# Uni-2_31.net
KiCad netlist of a schematic drawn in EAGLE
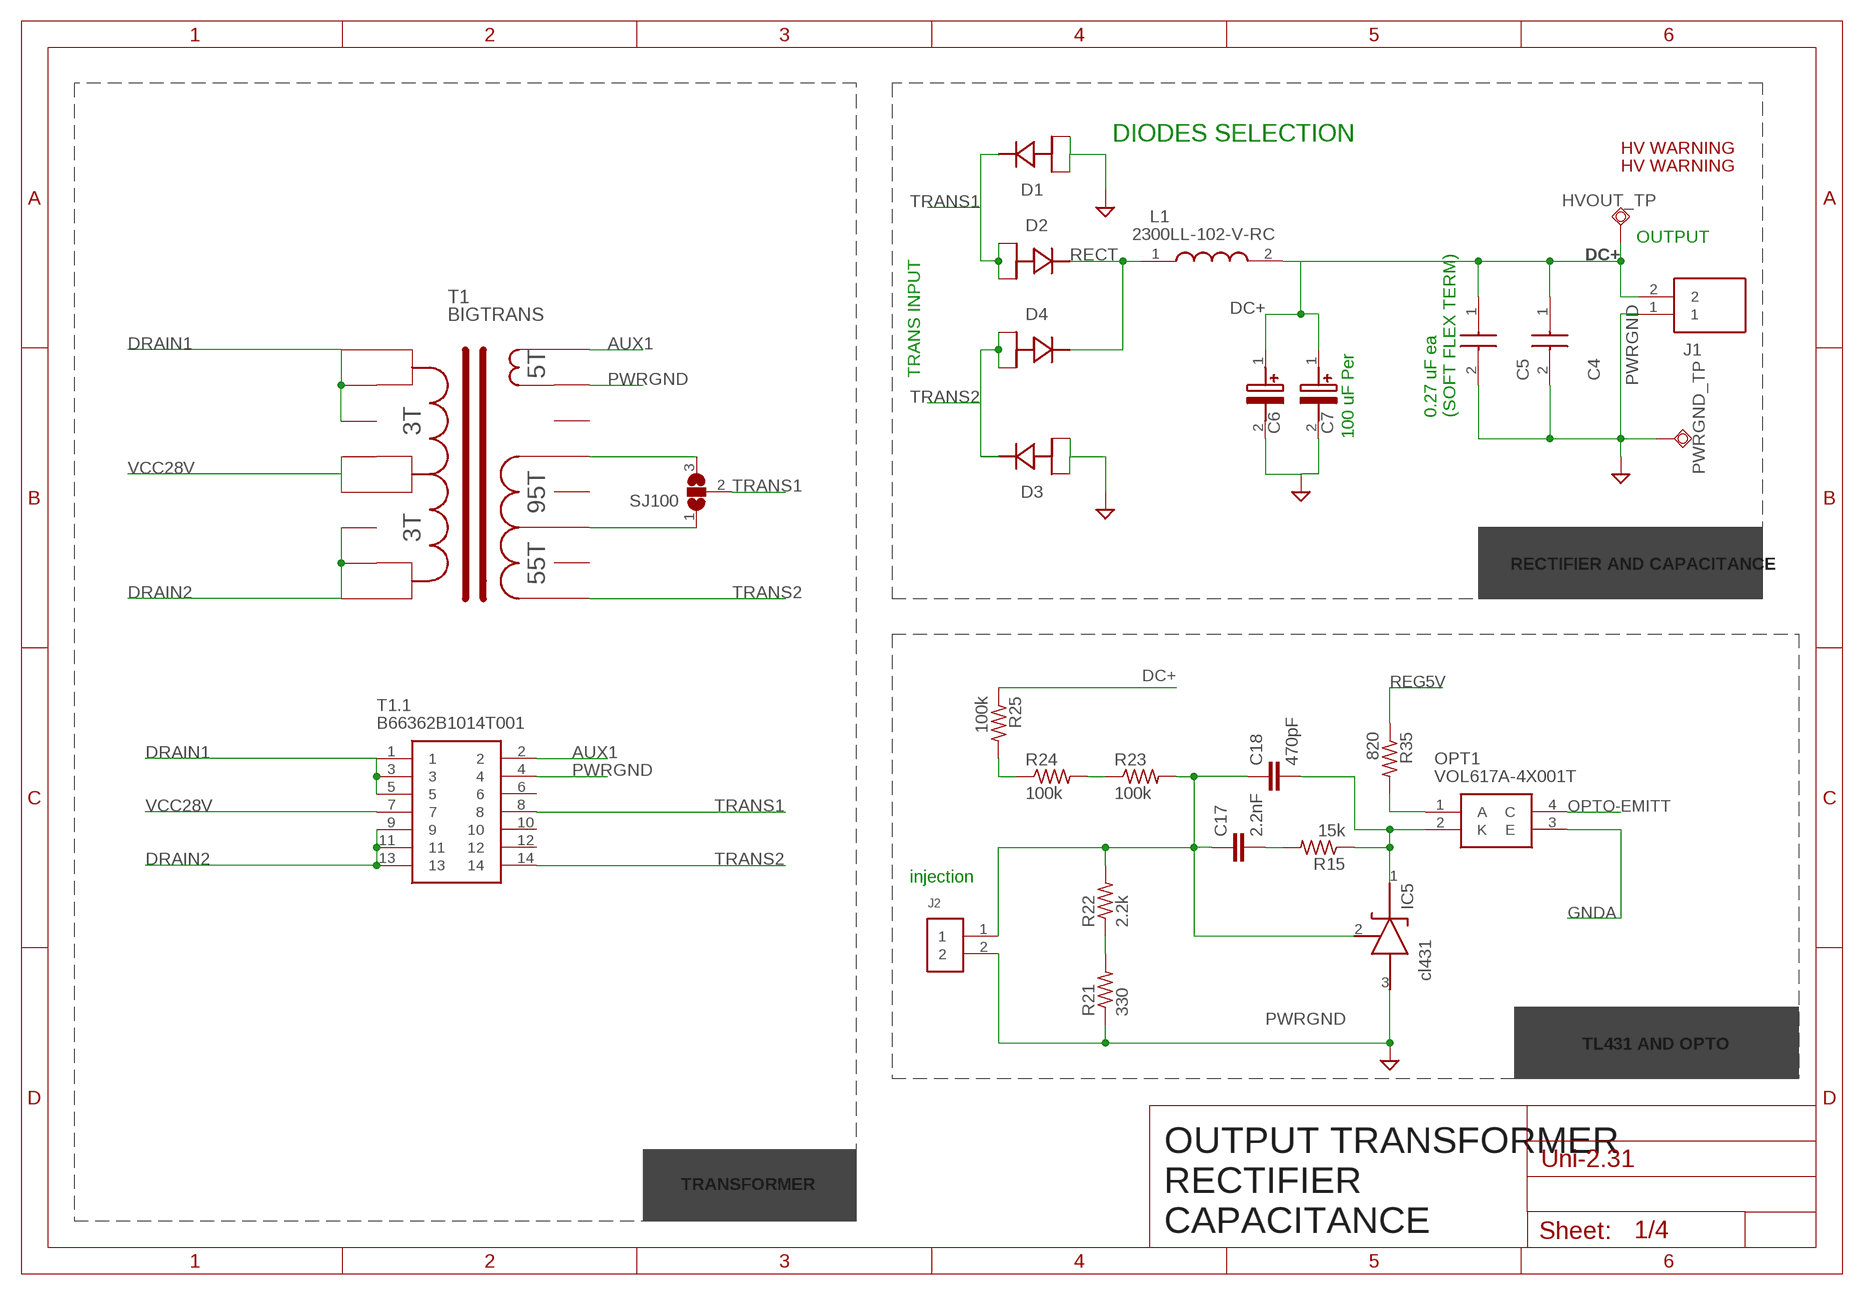
[diagram p0: schematic, sheet 1]
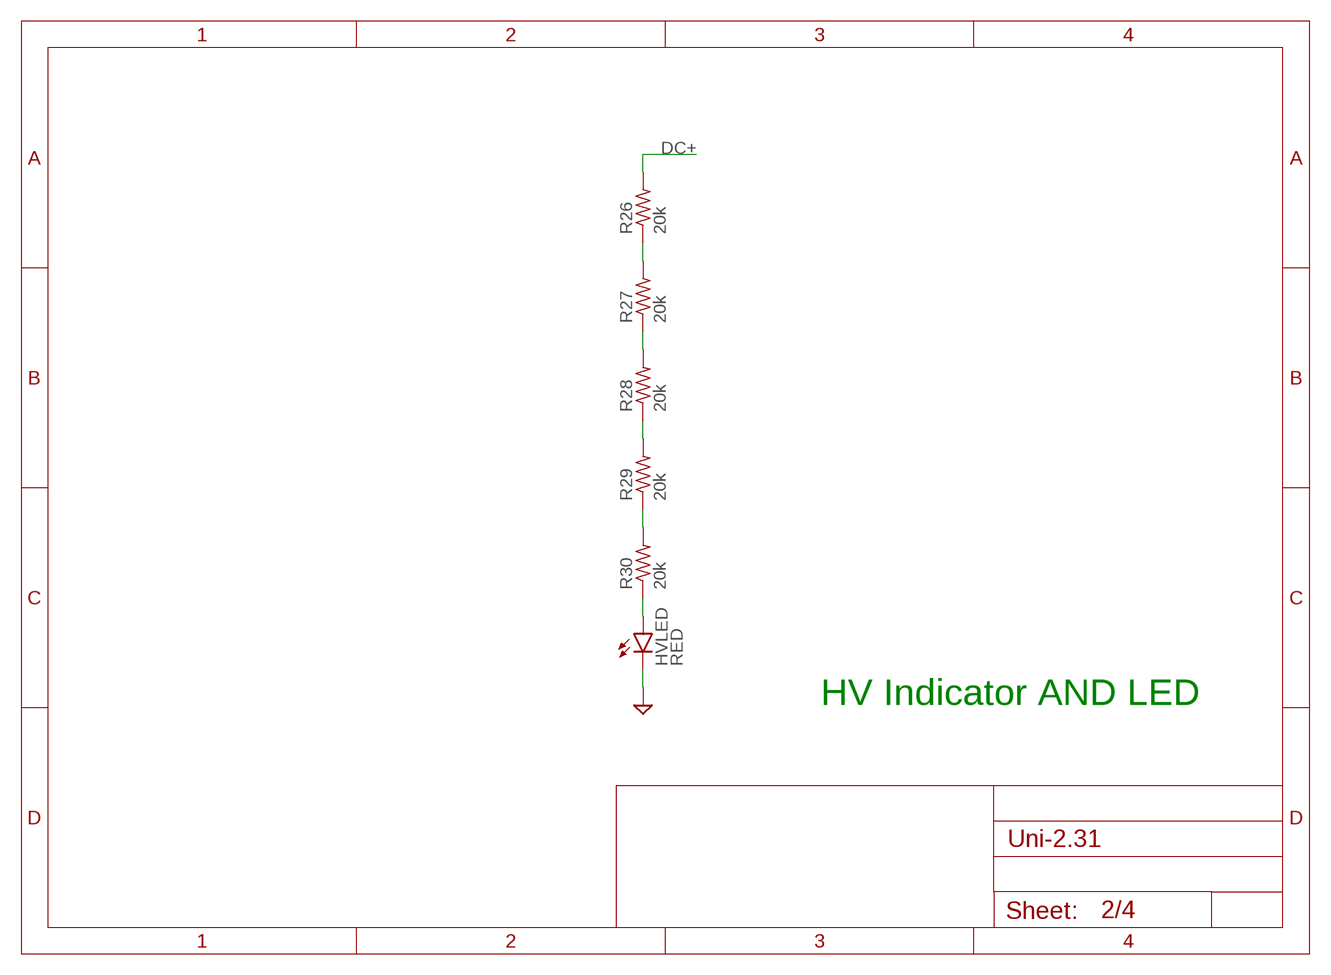
[diagram p1: schematic, sheet 2]
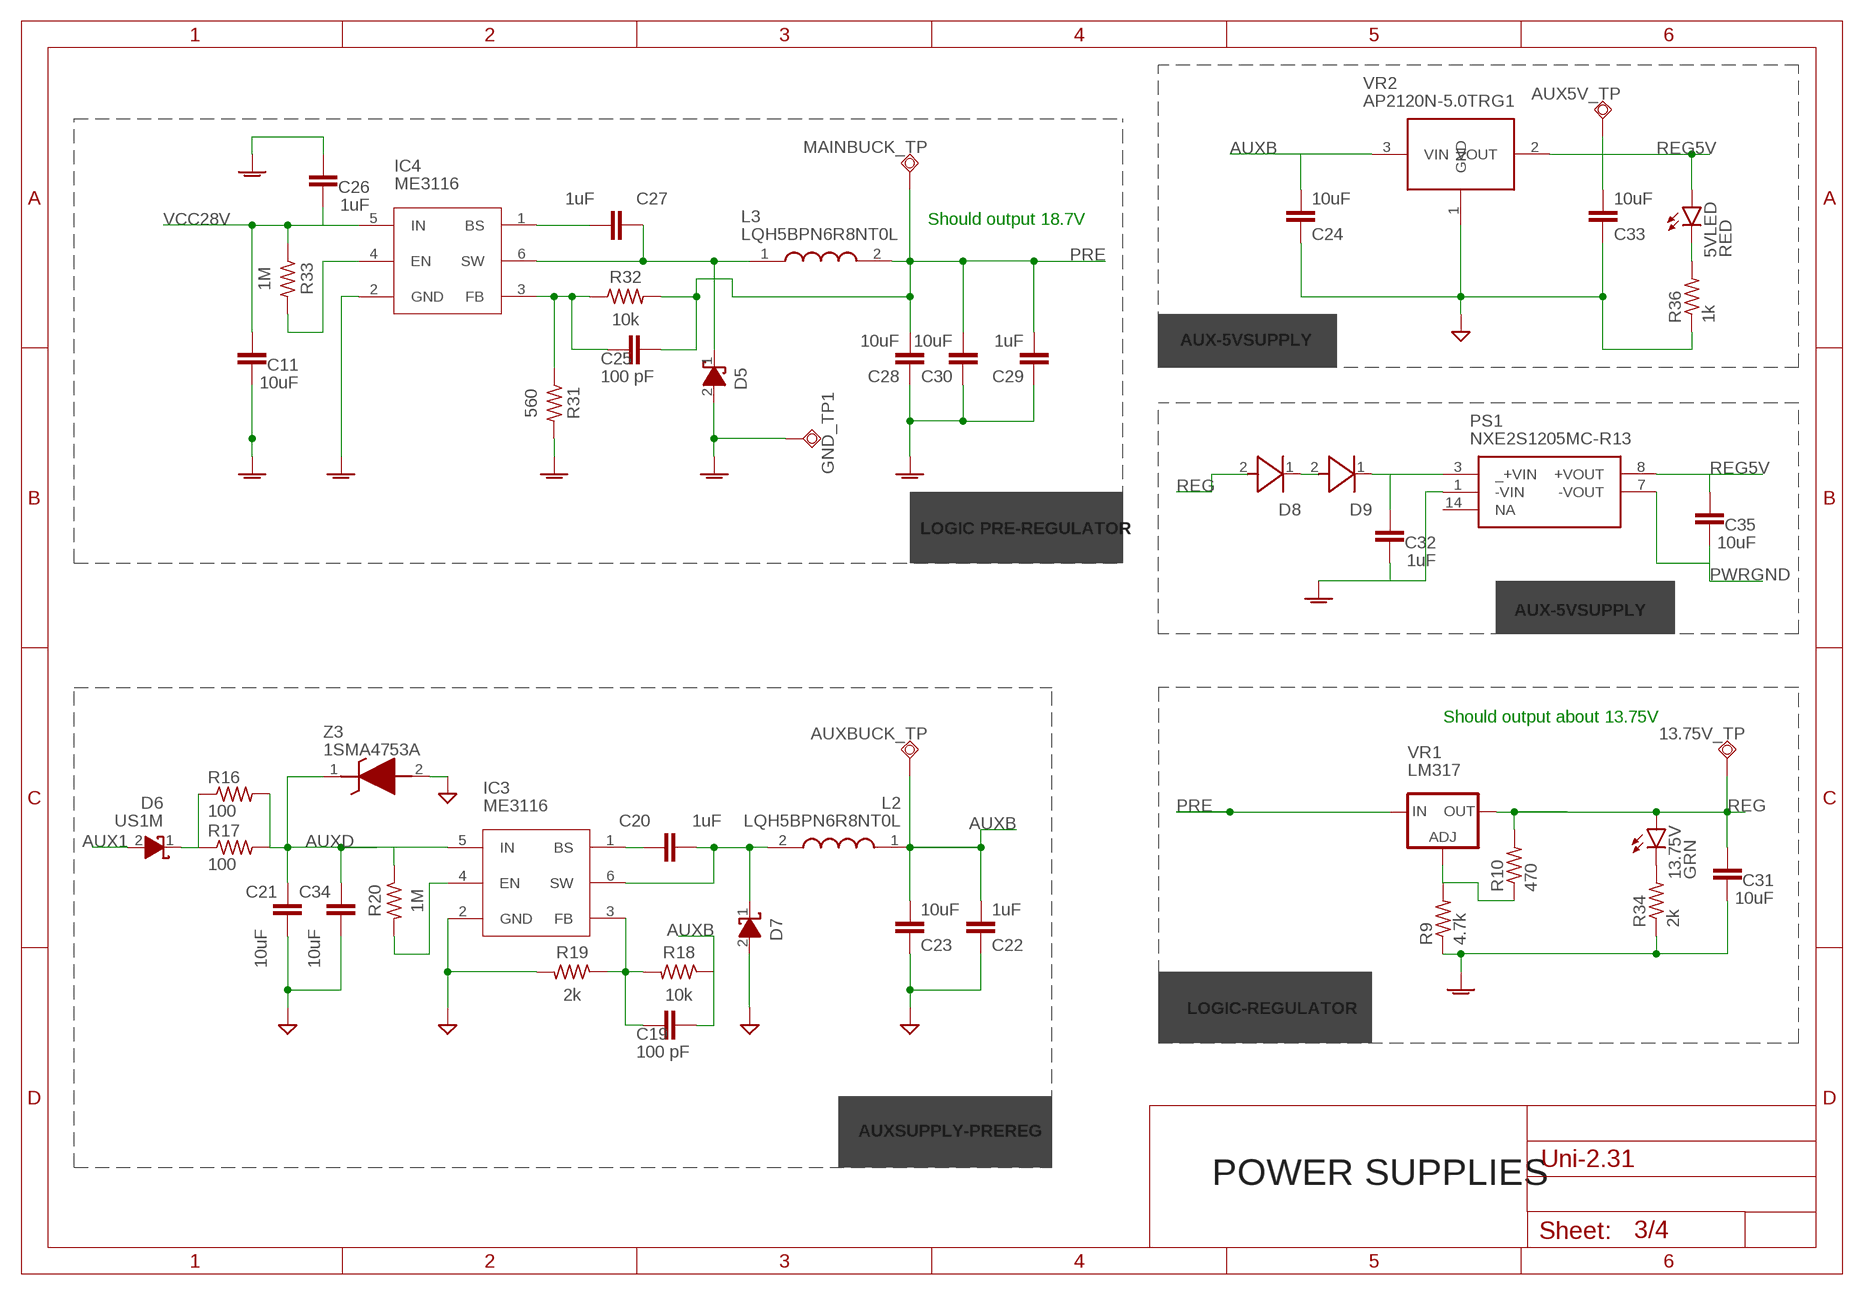
[diagram p2: schematic, sheet 3]
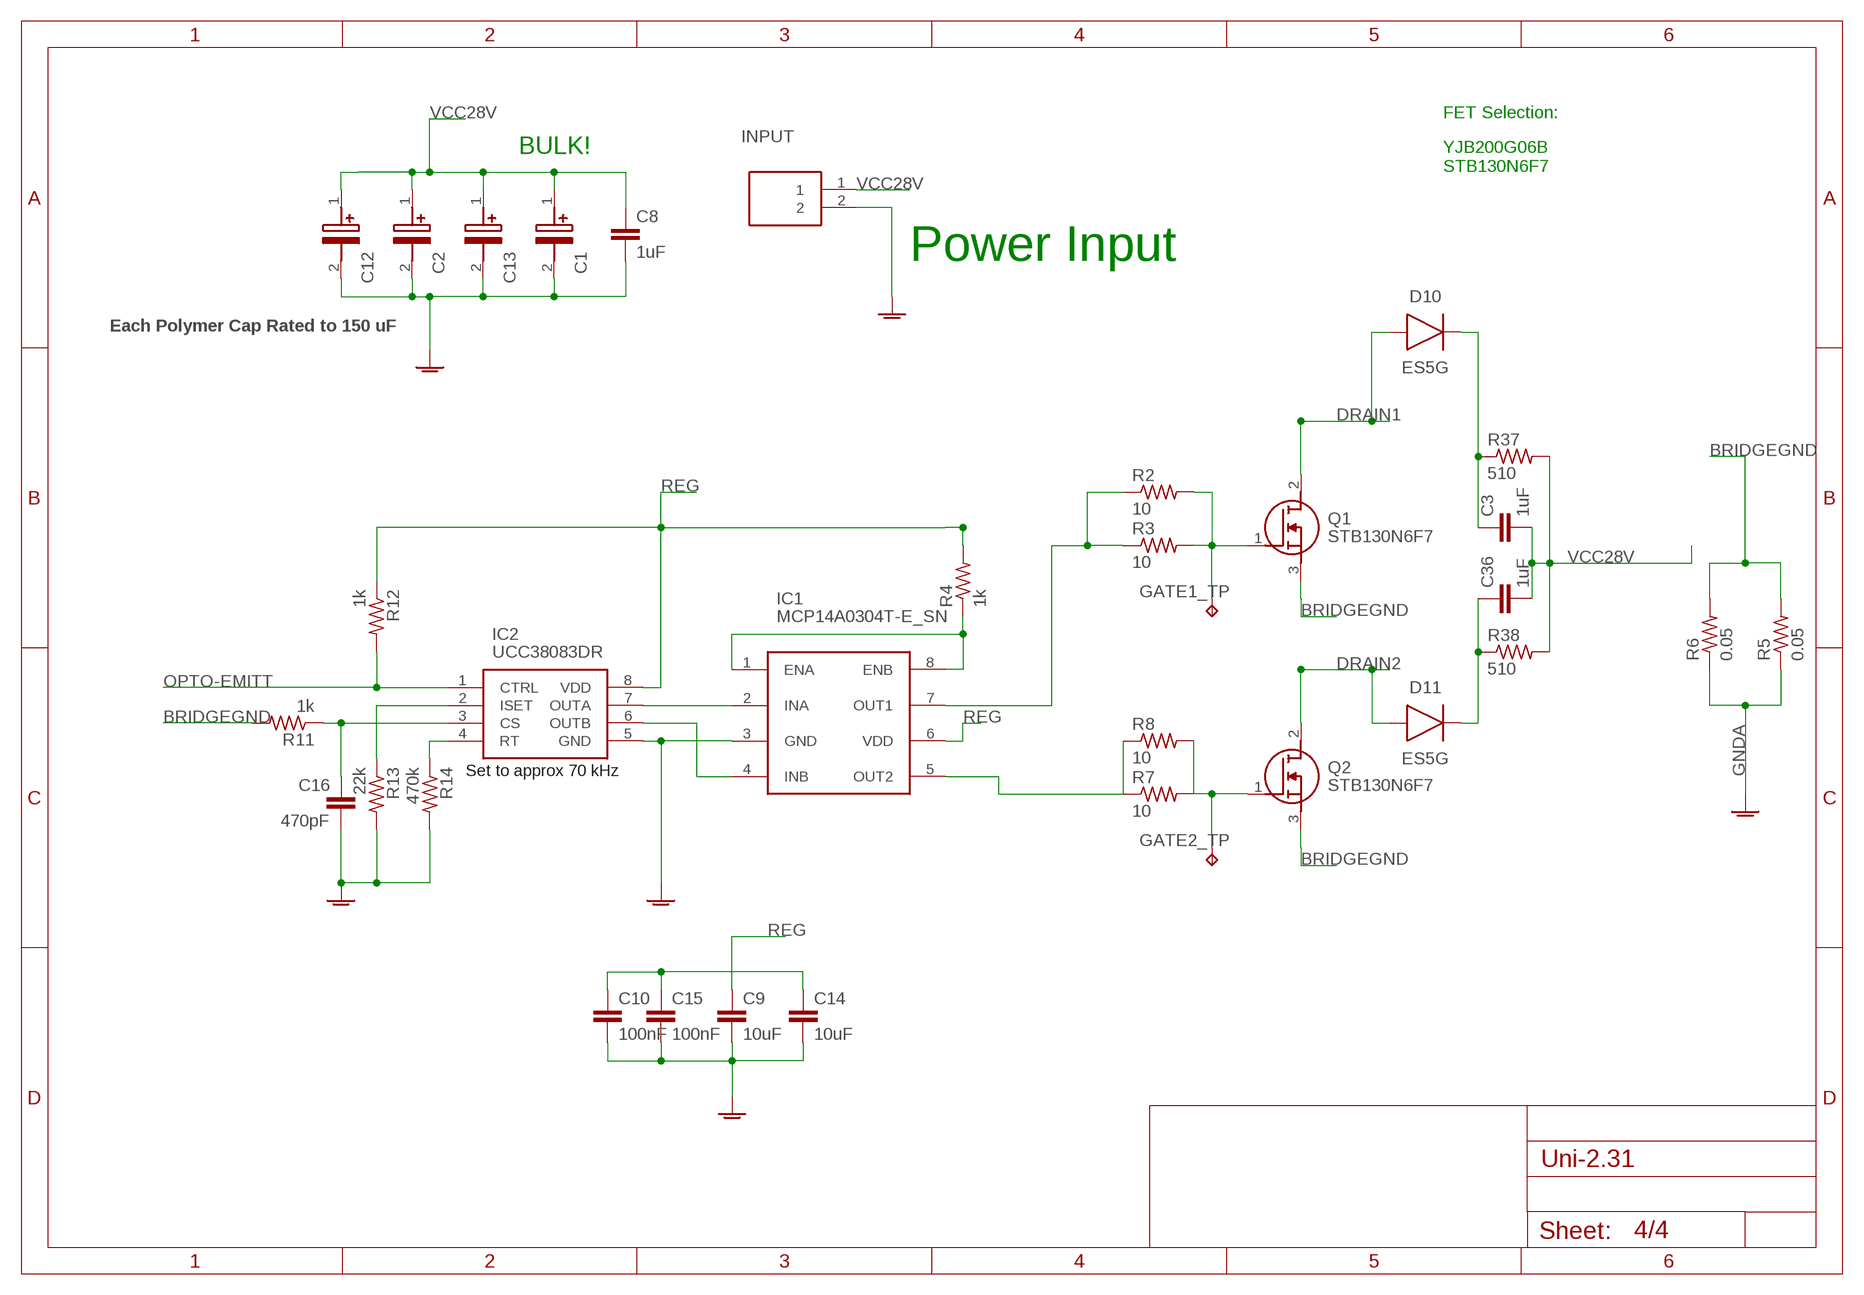
[diagram p3: schematic, sheet 4]

(export (version "E")
  (design (tool "Eeschema 10.0.6"))
  (components
    (comp (ref "HVLED")
      (value "RED")
      (footprint "eagle-import:CHIPLED_0805")
      (libsource (lib "eagle-import") (part "LEDCHIPLED_0805"))
    )
    (comp (ref "R26")
      (value "20k")
      (footprint "eagle-import:R1206")
      (libsource (lib "eagle-import") (part "R-US_R1206"))
    )
    (comp (ref "R27")
      (value "20k")
      (footprint "eagle-import:R1206")
      (libsource (lib "eagle-import") (part "R-US_R1206"))
    )
    (comp (ref "R28")
      (value "20k")
      (footprint "eagle-import:R1206")
      (libsource (lib "eagle-import") (part "R-US_R1206"))
    )
    (comp (ref "R29")
      (value "20k")
      (footprint "eagle-import:R1206")
      (libsource (lib "eagle-import") (part "R-US_R1206"))
    )
    (comp (ref "R30")
      (value "20k")
      (footprint "eagle-import:R1206")
      (libsource (lib "eagle-import") (part "R-US_R1206"))
    )
    (comp (ref "C1")
      (value "OVK151M1VTR-10131")
      (footprint "eagle-import:16SVF1000M")
      (libsource (lib "eagle-import") (part "OVK151M1VTR-10131"))
    )
    (comp (ref "C2")
      (value "OVK151M1VTR-10131")
      (footprint "eagle-import:16SVF1000M")
      (libsource (lib "eagle-import") (part "OVK151M1VTR-10131"))
    )
    (comp (ref "C3")
      (value "1uF")
      (footprint "eagle-import:C1206K")
      (libsource (lib "eagle-import") (part "rcl_334_C-EUC1206K"))
    )
    (comp (ref "C8")
      (value "1uF")
      (footprint "eagle-import:C0805K")
      (fields (field (name "LCSC_PART") "C440198"))
      (libsource (lib "eagle-import") (part "rcl_334_C-EUC0805K"))
    )
    (comp (ref "C9")
      (value "10uF")
      (footprint "eagle-import:C0603K")
      (fields (field (name "LCSC_PART") "C440198"))
      (libsource (lib "eagle-import") (part "rcl_334_C-EUC0603K"))
    )
    (comp (ref "C10")
      (value "100nF")
      (footprint "eagle-import:C0402")
      (fields (field (name "LCSC_PART") "C440198"))
      (libsource (lib "eagle-import") (part "rcl_334_C-EUC0402"))
    )
    (comp (ref "C12")
      (value "OVK151M1VTR-10131")
      (footprint "eagle-import:16SVF1000M")
      (libsource (lib "eagle-import") (part "OVK151M1VTR-10131"))
    )
    (comp (ref "C13")
      (value "OVK151M1VTR-10131")
      (footprint "eagle-import:16SVF1000M")
      (libsource (lib "eagle-import") (part "OVK151M1VTR-10131"))
    )
    (comp (ref "C14")
      (value "10uF")
      (footprint "eagle-import:C0603K")
      (fields (field (name "LCSC_PART") "C440198"))
      (libsource (lib "eagle-import") (part "rcl_334_C-EUC0603K"))
    )
    (comp (ref "C15")
      (value "100nF")
      (footprint "eagle-import:C0402")
      (fields (field (name "LCSC_PART") "C440198"))
      (libsource (lib "eagle-import") (part "rcl_334_C-EUC0402"))
    )
    (comp (ref "C16")
      (value "470pF")
      (footprint "eagle-import:C0603K")
      (fields (field (name "LCSC_PART") "C1620"))
      (libsource (lib "eagle-import") (part "rcl_334_C-EUC0603K"))
    )
    (comp (ref "C36")
      (value "1uF")
      (footprint "eagle-import:C1206K")
      (libsource (lib "eagle-import") (part "rcl_334_C-EUC1206K"))
    )
    (comp (ref "D10")
      (value "ES5G")
      (footprint "eagle-import:DIOM5336X265N")
      (fields (field (name "LCSC_PART") "C128705"))
      (libsource (lib "eagle-import") (part "DIODEDO-214AA(SMB)"))
    )
    (comp (ref "D11")
      (value "ES5G")
      (footprint "eagle-import:DIOM5336X265N")
      (libsource (lib "eagle-import") (part "DIODEDO-214AA(SMB)"))
    )
    (comp (ref "GATE1_TP")
      (value "TPTP13R")
      (footprint "eagle-import:TP13R")
      (libsource (lib "eagle-import") (part "TPTP13R"))
    )
    (comp (ref "GATE2_TP")
      (value "TPTP13R")
      (footprint "eagle-import:TP13R")
      (libsource (lib "eagle-import") (part "TPTP13R"))
    )
    (comp (ref "IC1")
      (value "MCP14A0304T-E_SN")
      (footprint "eagle-import:SOIC127P600X175-8N")
      (fields
        (field (name "MANUFACTURER_PART_NUMBER") "MCP14A0304T-E/SN")
        (field (name "MOUSER_PART_NUMBER") "579-MCP14A0304T-E/SN")
      )
      (libsource (lib "eagle-import") (part "MCP14A0304T-E_SN"))
    )
    (comp (ref "IC2")
      (value "UCC38083DR")
      (footprint "eagle-import:SOIC127P600X175-8N")
      (fields (field (name "MOUSER_PART_NUMBER") "595-UCC38083DR"))
      (libsource (lib "eagle-import") (part "UCC38083DR"))
    )
    (comp (ref "INPUT")
      (value "TB005-762-02BE")
      (footprint "eagle-import:TB00576202BE")
      (fields (field (name "MOUSER_PART_NUMBER") "490-TB005-762-02BE"))
      (libsource (lib "eagle-import") (part "TB005-762-02BE"))
    )
    (comp (ref "Q1")
      (value "STB130N6F7")
      (footprint "eagle-import:D2PAK")
      (libsource (lib "eagle-import") (part "STB130N6F7"))
    )
    (comp (ref "Q2")
      (value "STB130N6F7")
      (footprint "eagle-import:D2PAK")
      (libsource (lib "eagle-import") (part "STB130N6F7"))
    )
    (comp (ref "R2")
      (value "10")
      (footprint "eagle-import:R0805")
      (libsource (lib "eagle-import") (part "R-US_R0805"))
    )
    (comp (ref "R3")
      (value "10")
      (footprint "eagle-import:R0805")
      (libsource (lib "eagle-import") (part "R-US_R0805"))
    )
    (comp (ref "R4")
      (value "1k")
      (footprint "eagle-import:R0402")
      (libsource (lib "eagle-import") (part "R-US_R0402"))
    )
    (comp (ref "R5")
      (value "0.05")
      (footprint "eagle-import:R2512")
      (libsource (lib "eagle-import") (part "R-US_R2512"))
    )
    (comp (ref "R6")
      (value "0.05")
      (footprint "eagle-import:R2512")
      (libsource (lib "eagle-import") (part "R-US_R2512"))
    )
    (comp (ref "R7")
      (value "10")
      (footprint "eagle-import:R0805")
      (libsource (lib "eagle-import") (part "R-US_R0805"))
    )
    (comp (ref "R8")
      (value "10")
      (footprint "eagle-import:R0805")
      (libsource (lib "eagle-import") (part "R-US_R0805"))
    )
    (comp (ref "R11")
      (value "1k")
      (footprint "eagle-import:R0603")
      (fields (field (name "LCSC_PART") "C21190"))
      (libsource (lib "eagle-import") (part "R-US_R0603"))
    )
    (comp (ref "R12")
      (value "1k")
      (footprint "eagle-import:R0603")
      (fields (field (name "LCSC_PART") "C22975"))
      (libsource (lib "eagle-import") (part "R-US_R0603"))
    )
    (comp (ref "R13")
      (value "22k")
      (footprint "eagle-import:R0603")
      (fields (field (name "LCSC_PART") "C31850"))
      (libsource (lib "eagle-import") (part "R-US_R0603"))
    )
    (comp (ref "R14")
      (value "470k")
      (footprint "eagle-import:R0603")
      (fields (field (name "LCSC_PART") "C25811"))
      (libsource (lib "eagle-import") (part "R-US_R0603"))
    )
    (comp (ref "R37")
      (value "510")
      (footprint "eagle-import:R2512")
      (libsource (lib "eagle-import") (part "R-US_R2512"))
    )
    (comp (ref "R38")
      (value "510")
      (footprint "eagle-import:R2512")
      (libsource (lib "eagle-import") (part "R-US_R2512"))
    )
    (comp (ref "C4")
      (value "C1812C274KCRACAUTO")
      (footprint "eagle-import:C1812")
      (fields (field (name "MOUSER_PART_NUMBER") "80-C1812C274KCRAUTO"))
      (libsource (lib "eagle-import") (part "C1812C274KCRACAUTO"))
    )
    (comp (ref "C5")
      (value "C1812C274KCRACAUTO")
      (footprint "eagle-import:C1812")
      (fields (field (name "MOUSER_PART_NUMBER") "80-C1812C274KCRAUTO"))
      (libsource (lib "eagle-import") (part "C1812C274KCRACAUTO"))
    )
    (comp (ref "C6")
      (value "400BXW100MEFR18X25")
      (footprint "eagle-import:CAPPRD750W80D1825H2700")
      (libsource (lib "eagle-import") (part "400BXW100MEFR18X25"))
    )
    (comp (ref "C7")
      (value "400BXW100MEFR18X25")
      (footprint "eagle-import:CAPPRD750W80D1825H2700")
      (libsource (lib "eagle-import") (part "400BXW100MEFR18X25"))
    )
    (comp (ref "C17")
      (value "2.2nF")
      (footprint "eagle-import:C0603K")
      (libsource (lib "eagle-import") (part "rcl_334_C-EUC0603K"))
    )
    (comp (ref "C18")
      (value "470pF")
      (footprint "eagle-import:C0603K")
      (libsource (lib "eagle-import") (part "rcl_334_C-EUC0603K"))
    )
    (comp (ref "D1")
      (value "MURB1060CT")
      (footprint "eagle-import:STB20N95K5")
      (fields
        (field (name "MANUFACTURER_PART_NUMBER") "FERD20H60CG-TR")
        (field (name "MOUSER_PART_NUMBER") "511-FERD20H60CG-TR")
      )
      (libsource (lib "eagle-import") (part "FERD20H60CG-TR"))
    )
    (comp (ref "D2")
      (value "MURB1060CT")
      (footprint "eagle-import:STB20N95K5")
      (fields
        (field (name "MANUFACTURER_PART_NUMBER") "FERD20H60CG-TR")
        (field (name "MOUSER_PART_NUMBER") "511-FERD20H60CG-TR")
      )
      (libsource (lib "eagle-import") (part "FERD20H60CG-TR"))
    )
    (comp (ref "D3")
      (value "MURB1060CT")
      (footprint "eagle-import:STB20N95K5")
      (fields
        (field (name "MANUFACTURER_PART_NUMBER") "FERD20H60CG-TR")
        (field (name "MOUSER_PART_NUMBER") "511-FERD20H60CG-TR")
      )
      (libsource (lib "eagle-import") (part "FERD20H60CG-TR"))
    )
    (comp (ref "D4")
      (value "MURB1060CT")
      (footprint "eagle-import:STB20N95K5")
      (fields
        (field (name "MANUFACTURER_PART_NUMBER") "FERD20H60CG-TR")
        (field (name "MOUSER_PART_NUMBER") "511-FERD20H60CG-TR")
      )
      (libsource (lib "eagle-import") (part "FERD20H60CG-TR"))
    )
    (comp (ref "HVOUT_TP")
      (value "TPSQPAD1-13")
      (footprint "eagle-import:P1-13")
      (libsource (lib "eagle-import") (part "TPSQPAD1-13"))
    )
    (comp (ref "IC5")
      (value "cl431")
      (footprint "eagle-import:SOT95P237X112-3N")
      (fields
        (field (name "MANUFACTURER_PART_NUMBER") "TL431CL3T")
        (field (name "MOUSER_PART_NUMBER") "511-TL431CL3T")
      )
      (libsource (lib "eagle-import") (part "TL431CL3T"))
    )
    (comp (ref "J1")
      (value "TB005-762-02BE")
      (footprint "eagle-import:TB00576202BE")
      (fields (field (name "MOUSER_PART_NUMBER") "490-TB005-762-02BE"))
      (libsource (lib "eagle-import") (part "TB005-762-02BE"))
    )
    (comp (ref "J2")
      (value "61300211121")
      (footprint "eagle-import:61300211121")
      (fields
        (field (name "DIGI_KEY_PART_NUMBER") "732-5315-ND")
        (field (name "MANUFACTURER") "Wurth Electronics Inc.")
        (field (name "CREATED_BY") "PCBLayout.com")
      )
      (libsource (lib "eagle-import") (part "61300211121"))
    )
    (comp (ref "L1")
      (value "2300LL-102-V-RC")
      (footprint "eagle-import:2300LL102VRC")
      (fields (field (name "MOUSER_PART_NUMBER") "652-2300LL-102-V-RC"))
      (libsource (lib "eagle-import") (part "2300LL-102-V-RC"))
    )
    (comp (ref "OPT1")
      (value "VOL617A-4X001T")
      (footprint "eagle-import:SOP254P1015X230-4N")
      (fields (field (name "MOUSER_PART_NUMBER") "78-VOL617A-4X001T"))
      (libsource (lib "eagle-import") (part "VOL617A-4X001T"))
    )
    (comp (ref "PWRGND_TP")
      (value "TPSQPAD1-13")
      (footprint "eagle-import:P1-13")
      (libsource (lib "eagle-import") (part "TPSQPAD1-13"))
    )
    (comp (ref "R15")
      (value "15k")
      (footprint "eagle-import:R0603")
      (libsource (lib "eagle-import") (part "R-US_R0603"))
    )
    (comp (ref "R21")
      (value "330")
      (footprint "eagle-import:R0805")
      (libsource (lib "eagle-import") (part "R-US_R0805"))
    )
    (comp (ref "R22")
      (value "2.2k")
      (footprint "eagle-import:R0805")
      (libsource (lib "eagle-import") (part "R-US_R0805"))
    )
    (comp (ref "R23")
      (value "100k")
      (footprint "eagle-import:R1206")
      (libsource (lib "eagle-import") (part "R-US_R1206"))
    )
    (comp (ref "R24")
      (value "100k")
      (footprint "eagle-import:R1206")
      (libsource (lib "eagle-import") (part "R-US_R1206"))
    )
    (comp (ref "R25")
      (value "100k")
      (footprint "eagle-import:R1206")
      (libsource (lib "eagle-import") (part "R-US_R1206"))
    )
    (comp (ref "R35")
      (value "820")
      (footprint "eagle-import:R0603")
      (libsource (lib "eagle-import") (part "R-US_R0603"))
    )
    (comp (ref "SJ100")
      (value "SJ2WW")
      (footprint "eagle-import:SJ_2W")
      (libsource (lib "eagle-import") (part "SJ2WW"))
    )
    (comp (ref "T1")
      (value "BIGTRANS")
      (footprint "eagle-import:BIGTRANS!")
      (libsource (lib "eagle-import") (part "BIGTRANS"))
    )
    (comp (ref "T1.1")
      (value "B66362B1014T001")
      (footprint "eagle-import:B66362B1014T001")
      (fields (field (name "MOUSER_PART_NUMBER") "871-B66362B1014T001"))
      (libsource (lib "eagle-import") (part "B66362B1014T001"))
    )
    (comp (ref "U$3")
      (value "HV")
      (footprint "eagle-import:PSFBC_ELECTRIC_SHOCK")
      (libsource (lib "eagle-import") (part "HV"))
    )
    (comp (ref "U$4")
      (value "HV")
      (footprint "eagle-import:PSFBC_ELECTRIC_SHOCK")
      (libsource (lib "eagle-import") (part "HV"))
    )
    (comp (ref "5VLED")
      (value "RED")
      (footprint "eagle-import:CHIPLED_0805")
      (fields (field (name "LCSC_PART") "C72043"))
      (libsource (lib "eagle-import") (part "LEDCHIPLED_0805"))
    )
    (comp (ref "13.75V")
      (value "GRN")
      (footprint "eagle-import:CHIPLED_0805")
      (fields (field (name "LCSC_PART") "C72043"))
      (libsource (lib "eagle-import") (part "LEDCHIPLED_0805"))
    )
    (comp (ref "13.75V_TP")
      (value "TPSQPAD1-17")
      (footprint "eagle-import:P1-17")
      (libsource (lib "eagle-import") (part "TPSQPAD1-17"))
    )
    (comp (ref "AUX5V_TP")
      (value "TPSQPAD1-17")
      (footprint "eagle-import:P1-17")
      (libsource (lib "eagle-import") (part "TPSQPAD1-17"))
    )
    (comp (ref "AUXBUCK_TP")
      (value "TPSQPAD1-17")
      (footprint "eagle-import:P1-17")
      (libsource (lib "eagle-import") (part "TPSQPAD1-17"))
    )
    (comp (ref "C11")
      (value "10uF")
      (footprint "eagle-import:C0805K")
      (fields (field (name "LCSC_PART") "C440198"))
      (libsource (lib "eagle-import") (part "C-EUC0805K"))
    )
    (comp (ref "C19")
      (value "100 pF")
      (footprint "eagle-import:C0402K")
      (fields (field (name "LCSC_PART") "C1546"))
      (libsource (lib "eagle-import") (part "rcl_334_C-EUC0402K"))
    )
    (comp (ref "C20")
      (value "1uF")
      (footprint "eagle-import:C0603K")
      (fields (field (name "LCSC_PART") "C14663"))
      (libsource (lib "eagle-import") (part "rcl_334_C-EUC0603K"))
    )
    (comp (ref "C21")
      (value "10uF")
      (footprint "eagle-import:C0805K")
      (libsource (lib "eagle-import") (part "rcl_334_C-EUC0805K"))
    )
    (comp (ref "C22")
      (value "1uF")
      (footprint "eagle-import:C0402")
      (fields (field (name "LCSC_PART") "C440198"))
      (libsource (lib "eagle-import") (part "rcl_334_C-EUC0402"))
    )
    (comp (ref "C23")
      (value "10uF")
      (footprint "eagle-import:C0603K")
      (fields (field (name "LCSC_PART") "C440198"))
      (libsource (lib "eagle-import") (part "rcl_334_C-EUC0603K"))
    )
    (comp (ref "C24")
      (value "10uF")
      (footprint "eagle-import:C0603K")
      (fields (field (name "LCSC_PART") "C440198"))
      (libsource (lib "eagle-import") (part "rcl_334_C-EUC0603K"))
    )
    (comp (ref "C25")
      (value "100 pF")
      (footprint "eagle-import:C0402K")
      (fields (field (name "LCSC_PART") "C1546"))
      (libsource (lib "eagle-import") (part "rcl_334_C-EUC0402K"))
    )
    (comp (ref "C26")
      (value "1uF")
      (footprint "eagle-import:C0603K")
      (fields (field (name "LCSC_PART") "C440198"))
      (libsource (lib "eagle-import") (part "rcl_334_C-EUC0603K"))
    )
    (comp (ref "C27")
      (value "1uF")
      (footprint "eagle-import:C0603K")
      (fields (field (name "LCSC_PART") "C14663"))
      (libsource (lib "eagle-import") (part "rcl_334_C-EUC0603K"))
    )
    (comp (ref "C28")
      (value "10uF")
      (footprint "eagle-import:C0603K")
      (fields (field (name "LCSC_PART") "C440198"))
      (libsource (lib "eagle-import") (part "C-EUC0603K"))
    )
    (comp (ref "C29")
      (value "1uF")
      (footprint "eagle-import:C0603K")
      (fields (field (name "LCSC_PART") "C440198"))
      (libsource (lib "eagle-import") (part "C-EUC0603K"))
    )
    (comp (ref "C30")
      (value "10uF")
      (footprint "eagle-import:C0603K")
      (fields (field (name "LCSC_PART") "C440198"))
      (libsource (lib "eagle-import") (part "C-EUC0603K"))
    )
    (comp (ref "C31")
      (value "10uF")
      (footprint "eagle-import:C0603K")
      (fields (field (name "LCSC_PART") "C440198"))
      (libsource (lib "eagle-import") (part "C-EUC0603K"))
    )
    (comp (ref "C32")
      (value "1uF")
      (footprint "eagle-import:C0603K")
      (fields (field (name "LCSC_PART") "C440198"))
      (libsource (lib "eagle-import") (part "rcl_334_C-EUC0603K"))
    )
    (comp (ref "C33")
      (value "10uF")
      (footprint "eagle-import:C0603K")
      (libsource (lib "eagle-import") (part "rcl_334_C-EUC0603K"))
    )
    (comp (ref "C34")
      (value "10uF")
      (footprint "eagle-import:C0805K")
      (libsource (lib "eagle-import") (part "rcl_334_C-EUC0805K"))
    )
    (comp (ref "C35")
      (value "10uF")
      (footprint "eagle-import:C0603K")
      (fields (field (name "LCSC_PART") "C440198"))
      (libsource (lib "eagle-import") (part "rcl_334_C-EUC0603K"))
    )
    (comp (ref "D5")
      (value "SCHOTTKY")
      (footprint "eagle-import:DIOM5127X229N")
      (fields
        (field (name "MANUFACTURER_PART_NUMBER") "SS16HE3_B/H")
        (field (name "MOUSER_PART_NUMBER") "78-SS16HE3_B/H")
        (field (name "LCSC_PART") "C22452")
      )
      (libsource (lib "eagle-import") (part "SCHOTTKY"))
    )
    (comp (ref "D6")
      (value "US1M")
      (footprint "eagle-import:DIOM5127X229N")
      (fields
        (field (name "MANUFACTURER_PART_NUMBER") "SS16HE3_B/H")
        (field (name "MOUSER_PART_NUMBER") "78-SS16HE3_B/H")
      )
      (libsource (lib "eagle-import") (part "SCHOTTKY"))
    )
    (comp (ref "D7")
      (value "SCHOTTKY")
      (footprint "eagle-import:DIOM5127X229N")
      (fields
        (field (name "MANUFACTURER_PART_NUMBER") "SS16HE3_B/H")
        (field (name "MOUSER_PART_NUMBER") "78-SS16HE3_B/H")
        (field (name "LCSC_PART") "C22452")
      )
      (libsource (lib "eagle-import") (part "SCHOTTKY"))
    )
    (comp (ref "D8")
      (value "SM4007PL")
      (footprint "eagle-import:SOD3716X145N")
      (fields
        (field (name "MANUFACTURER_PART_NUMBER") "1N4148W-7-F")
        (field (name "MOUSER_PART_NUMBER") "621-1N4148W-F")
        (field (name "LCSC_PART") "C64898")
      )
      (libsource (lib "eagle-import") (part "1N4148W-7-F"))
    )
    (comp (ref "D9")
      (value "SM4007PL")
      (footprint "eagle-import:SOD3716X145N")
      (fields
        (field (name "MANUFACTURER_PART_NUMBER") "1N4148W-7-F")
        (field (name "MOUSER_PART_NUMBER") "621-1N4148W-F")
        (field (name "LCSC_PART") "C64898")
      )
      (libsource (lib "eagle-import") (part "1N4148W-7-F"))
    )
    (comp (ref "GND_TP1")
      (value "TPSQPAD1-13")
      (footprint "eagle-import:P1-13")
      (libsource (lib "eagle-import") (part "TPSQPAD1-13"))
    )
    (comp (ref "IC3")
      (value "ME3116")
      (footprint "eagle-import:SOT95P280X100-6N")
      (fields (field (name "LCSC_PART") "C97643"))
      (libsource (lib "eagle-import") (part "ME3116"))
    )
    (comp (ref "IC4")
      (value "ME3116")
      (footprint "eagle-import:SOT95P280X100-6N")
      (fields (field (name "LCSC_PART") "C97643"))
      (libsource (lib "eagle-import") (part "ME3116"))
    )
    (comp (ref "L2")
      (value "LQH5BPN6R8NT0L")
      (footprint "eagle-import:LQH5BPB100MT0L")
      (fields (field (name "MOUSER_PART_NUMBER") "81-LQH5BPN6R8NT0L0L"))
      (libsource (lib "eagle-import") (part "LQH5BPN6R8NT0L"))
    )
    (comp (ref "L3")
      (value "LQH5BPN6R8NT0L")
      (footprint "eagle-import:LQH5BPB100MT0L")
      (fields (field (name "MOUSER_PART_NUMBER") "81-LQH5BPN6R8NT0L0L"))
      (libsource (lib "eagle-import") (part "LQH5BPN6R8NT0L"))
    )
    (comp (ref "MAINBUCK_TP")
      (value "TPSQPAD1-17")
      (footprint "eagle-import:P1-17")
      (libsource (lib "eagle-import") (part "TPSQPAD1-17"))
    )
    (comp (ref "PS1")
      (value "NXE2S1205MC-R13")
      (footprint "eagle-import:NXE2S1205MCR13")
      (fields (field (name "MOUSER_PART_NUMBER") "580-NXE2S1205MC-R13"))
      (libsource (lib "eagle-import") (part "NXE2S1205MC-R13"))
    )
    (comp (ref "R9")
      (value "4.7k")
      (footprint "eagle-import:R0603")
      (fields (field (name "LCSC_PART") "C22975"))
      (libsource (lib "eagle-import") (part "R-US_R0603"))
    )
    (comp (ref "R10")
      (value "470")
      (footprint "eagle-import:R0603")
      (fields (field (name "LCSC_PART") "C22975"))
      (libsource (lib "eagle-import") (part "R-US_R0603"))
    )
    (comp (ref "R16")
      (value "100")
      (footprint "eagle-import:R1206")
      (libsource (lib "eagle-import") (part "R-US_R1206"))
    )
    (comp (ref "R17")
      (value "100")
      (footprint "eagle-import:R1206")
      (libsource (lib "eagle-import") (part "R-US_R1206"))
    )
    (comp (ref "R18")
      (value "10k")
      (footprint "eagle-import:R0402")
      (fields (field (name "LCSC_PART") "C25779"))
      (libsource (lib "eagle-import") (part "R-US_R0402"))
    )
    (comp (ref "R19")
      (value "2k")
      (footprint "eagle-import:R0402")
      (fields (field (name "LCSC_PART") "C25779"))
      (libsource (lib "eagle-import") (part "R-US_R0402"))
    )
    (comp (ref "R20")
      (value "1M")
      (footprint "eagle-import:R0402")
      (fields (field (name "LCSC_PART") "C25741") (field (name "SPICEPREFIX") "R"))
      (libsource (lib "eagle-import") (part "R-US_R0402"))
    )
    (comp (ref "R31")
      (value "560")
      (footprint "eagle-import:R0603")
      (fields (field (name "LCSC_PART") "C4177") (field (name "SPICEPREFIX") "R"))
      (libsource (lib "eagle-import") (part "R-US_R0603"))
    )
    (comp (ref "R32")
      (value "10k")
      (footprint "eagle-import:R0402")
      (fields (field (name "LCSC_PART") "C25779"))
      (libsource (lib "eagle-import") (part "R-US_R0402"))
    )
    (comp (ref "R33")
      (value "1M")
      (footprint "eagle-import:R0402")
      (fields (field (name "LCSC_PART") "C25741") (field (name "SPICEPREFIX") "R"))
      (libsource (lib "eagle-import") (part "R-US_R0402"))
    )
    (comp (ref "R34")
      (value "2k")
      (footprint "eagle-import:R0603")
      (fields (field (name "LCSC_PART") "C22975"))
      (libsource (lib "eagle-import") (part "R-US_R0603"))
    )
    (comp (ref "R36")
      (value "1k")
      (footprint "eagle-import:R0603")
      (fields (field (name "LCSC_PART") "C22975"))
      (libsource (lib "eagle-import") (part "R-US_R0603"))
    )
    (comp (ref "VR1")
      (value "LM317")
      (footprint "eagle-import:DPACK")
      (libsource (lib "eagle-import") (part "LM317?MBDT"))
    )
    (comp (ref "VR2")
      (value "AP2120N-5.0TRG1")
      (footprint "eagle-import:SOT95P240X120-3N")
      (fields (field (name "MOUSER_PART_NUMBER") "621-AP2120N-5.0TRG1"))
      (libsource (lib "eagle-import") (part "AP2120N-5.0TRG1"))
    )
    (comp (ref "Z3")
      (value "1SMA4753A")
      (footprint "eagle-import:DIOM5226X220N")
      (fields
        (field (name "MANUFACTURER_PART_NUMBER") "1SMA5942BT3G")
        (field (name "MOUSER_PART_NUMBER") "863-1SMA5942BT3G")
        (field (name "LCSC_PART") "C362284")
      )
      (libsource (lib "eagle-import") (part "1SMA5942BT3G"))
    )
  )
  (nets
    (net (code "1") (name "AUX1") (class "Default")
      (node (ref "D6") (pin "2") (pinfunction "A_2") (pintype "bidirectional"))
      (node (ref "T1") (pin "16") (pinfunction "16_16") (pintype "bidirectional"))
      (node (ref "T1.1") (pin "2") (pinfunction "2_2") (pintype "bidirectional"))
    )
    (net (code "2") (name "AUXB") (class "Default")
      (node (ref "AUXBUCK_TP") (pin "TP") (pinfunction "TP_TP") (pintype "input"))
      (node (ref "C19") (pin "1") (pinfunction "1_1") (pintype "passive"))
      (node (ref "C22") (pin "2") (pinfunction "2_2") (pintype "passive"))
      (node (ref "C23") (pin "2") (pinfunction "2_2") (pintype "passive"))
      (node (ref "C24") (pin "2") (pinfunction "2_2") (pintype "passive"))
      (node (ref "L2") (pin "1") (pinfunction "1_1") (pintype "bidirectional"))
      (node (ref "R18") (pin "1") (pinfunction "1_1") (pintype "passive"))
      (node (ref "VR2") (pin "3") (pinfunction "VIN_3") (pintype "bidirectional"))
    )
    (net (code "3") (name "AUXD") (class "Default")
      (node (ref "C21") (pin "1") (pinfunction "1_1") (pintype "passive"))
      (node (ref "C34") (pin "1") (pinfunction "1_1") (pintype "passive"))
      (node (ref "IC3") (pin "5") (pinfunction "IN_5") (pintype "bidirectional"))
      (node (ref "R16") (pin "2") (pinfunction "2_2") (pintype "passive"))
      (node (ref "R17") (pin "2") (pinfunction "2_2") (pintype "passive"))
      (node (ref "R20") (pin "1") (pinfunction "1_1") (pintype "passive"))
      (node (ref "Z3") (pin "1") (pinfunction "K_1") (pintype "bidirectional"))
    )
    (net (code "4") (name "BRIDGEGND") (class "Default")
      (node (ref "Q1") (pin "3") (pinfunction "S_3") (pintype "bidirectional"))
      (node (ref "Q2") (pin "3") (pinfunction "S_3") (pintype "bidirectional"))
      (node (ref "R11") (pin "2") (pinfunction "2_2") (pintype "passive"))
      (node (ref "R5") (pin "2") (pinfunction "2_2") (pintype "passive"))
      (node (ref "R6") (pin "2") (pinfunction "2_2") (pintype "passive"))
    )
    (net (code "5") (name "DC+") (class "Default")
      (node (ref "C4") (pin "1") (pinfunction "1_1") (pintype "bidirectional"))
      (node (ref "C5") (pin "1") (pinfunction "1_1") (pintype "bidirectional"))
      (node (ref "C6") (pin "1") (pinfunction "+_1") (pintype "bidirectional"))
      (node (ref "C7") (pin "1") (pinfunction "+_1") (pintype "bidirectional"))
      (node (ref "HVOUT_TP") (pin "TP") (pinfunction "TP_TP") (pintype "input"))
      (node (ref "J1") (pin "2") (pinfunction "2_2") (pintype "bidirectional"))
      (node (ref "L1") (pin "2") (pinfunction "2_2") (pintype "bidirectional"))
      (node (ref "R25") (pin "1") (pinfunction "1_1") (pintype "passive"))
      (node (ref "R26") (pin "2") (pinfunction "2_2") (pintype "passive"))
    )
    (net (code "6") (name "DRAIN1") (class "Default")
      (node (ref "D10") (pin "2") (pinfunction "A_2") (pintype "passive"))
      (node (ref "Q1") (pin "2") (pinfunction "D_2") (pintype "bidirectional"))
      (node (ref "T1") (pin "6") (pinfunction "6_6") (pintype "bidirectional"))
      (node (ref "T1") (pin "7") (pinfunction "7_7") (pintype "bidirectional"))
      (node (ref "T1") (pin "8") (pinfunction "8_8") (pintype "bidirectional"))
      (node (ref "T1.1") (pin "1") (pinfunction "1_1") (pintype "bidirectional"))
      (node (ref "T1.1") (pin "3") (pinfunction "3_3") (pintype "bidirectional"))
      (node (ref "T1.1") (pin "5") (pinfunction "5_5") (pintype "bidirectional"))
    )
    (net (code "7") (name "DRAIN2") (class "Default")
      (node (ref "D11") (pin "2") (pinfunction "A_2") (pintype "passive"))
      (node (ref "Q2") (pin "2") (pinfunction "D_2") (pintype "bidirectional"))
      (node (ref "T1") (pin "1") (pinfunction "1_1") (pintype "bidirectional"))
      (node (ref "T1") (pin "2") (pinfunction "2_2") (pintype "bidirectional"))
      (node (ref "T1") (pin "3") (pinfunction "3_3") (pintype "bidirectional"))
      (node (ref "T1.1") (pin "11") (pinfunction "11_11") (pintype "bidirectional"))
      (node (ref "T1.1") (pin "13") (pinfunction "13_13") (pintype "bidirectional"))
      (node (ref "T1.1") (pin "9") (pinfunction "9_9") (pintype "bidirectional"))
    )
    (net (code "8") (name "GNDA") (class "Default")
      (node (ref "C1") (pin "2") (pinfunction "-_2") (pintype "bidirectional"))
      (node (ref "C10") (pin "2") (pinfunction "2_2") (pintype "passive"))
      (node (ref "C11") (pin "1") (pinfunction "1_1") (pintype "passive"))
      (node (ref "C12") (pin "2") (pinfunction "-_2") (pintype "bidirectional"))
      (node (ref "C13") (pin "2") (pinfunction "-_2") (pintype "bidirectional"))
      (node (ref "C14") (pin "2") (pinfunction "2_2") (pintype "passive"))
      (node (ref "C15") (pin "2") (pinfunction "2_2") (pintype "passive"))
      (node (ref "C16") (pin "2") (pinfunction "2_2") (pintype "passive"))
      (node (ref "C2") (pin "2") (pinfunction "-_2") (pintype "bidirectional"))
      (node (ref "C26") (pin "2") (pinfunction "2_2") (pintype "passive"))
      (node (ref "C28") (pin "1") (pinfunction "1_1") (pintype "passive"))
      (node (ref "C29") (pin "1") (pinfunction "1_1") (pintype "passive"))
      (node (ref "C30") (pin "1") (pinfunction "1_1") (pintype "passive"))
      (node (ref "C31") (pin "1") (pinfunction "1_1") (pintype "passive"))
      (node (ref "C32") (pin "1") (pinfunction "1_1") (pintype "passive"))
      (node (ref "C8") (pin "2") (pinfunction "2_2") (pintype "passive"))
      (node (ref "C9") (pin "2") (pinfunction "2_2") (pintype "passive"))
      (node (ref "D5") (pin "2") (pinfunction "A_2") (pintype "bidirectional"))
      (node (ref "GND_TP1") (pin "TP") (pinfunction "TP_TP") (pintype "input"))
      (node (ref "IC1") (pin "3") (pinfunction "GND_3") (pintype "bidirectional"))
      (node (ref "IC2") (pin "5") (pinfunction "GND_5") (pintype "bidirectional"))
      (node (ref "IC4") (pin "2") (pinfunction "GND_2") (pintype "bidirectional"))
      (node (ref "INPUT") (pin "2") (pinfunction "2_2") (pintype "bidirectional"))
      (node (ref "OPT1") (pin "3") (pinfunction "E_3") (pintype "bidirectional"))
      (node (ref "PS1") (pin "1") (pinfunction "-VIN_1") (pintype "bidirectional"))
      (node (ref "R13") (pin "2") (pinfunction "2_2") (pintype "passive"))
      (node (ref "R14") (pin "2") (pinfunction "2_2") (pintype "passive"))
      (node (ref "R31") (pin "2") (pinfunction "2_2") (pintype "passive"))
      (node (ref "R34") (pin "1") (pinfunction "1_1") (pintype "passive"))
      (node (ref "R5") (pin "1") (pinfunction "1_1") (pintype "passive"))
      (node (ref "R6") (pin "1") (pinfunction "1_1") (pintype "passive"))
      (node (ref "R9") (pin "1") (pinfunction "1_1") (pintype "passive"))
    )
    (net (code "9") (name "Net-(5VLED-PadC)") (class "Default")
      (node (ref "5VLED") (pin "C") (pinfunction "C_C") (pintype "passive"))
      (node (ref "R36") (pin "2") (pinfunction "2_2") (pintype "passive"))
    )
    (net (code "10") (name "Net-(13.75V-PadC)") (class "Default")
      (node (ref "13.75V") (pin "C") (pinfunction "C_C") (pintype "passive"))
      (node (ref "R34") (pin "2") (pinfunction "2_2") (pintype "passive"))
    )
    (net (code "11") (name "Net-(C17-Pad2)") (class "Default")
      (node (ref "C17") (pin "2") (pinfunction "2_2") (pintype "passive"))
      (node (ref "R15") (pin "2") (pinfunction "2_2") (pintype "passive"))
    )
    (net (code "12") (name "Net-(D5-K)") (class "Default")
      (node (ref "C27") (pin "1") (pinfunction "1_1") (pintype "passive"))
      (node (ref "D5") (pin "1") (pinfunction "K_1") (pintype "bidirectional"))
      (node (ref "IC4") (pin "6") (pinfunction "SW_6") (pintype "bidirectional"))
      (node (ref "L3") (pin "1") (pinfunction "1_1") (pintype "bidirectional"))
    )
    (net (code "13") (name "Net-(D6-K)") (class "Default")
      (node (ref "D6") (pin "1") (pinfunction "K_1") (pintype "bidirectional"))
      (node (ref "R16") (pin "1") (pinfunction "1_1") (pintype "passive"))
      (node (ref "R17") (pin "1") (pinfunction "1_1") (pintype "passive"))
    )
    (net (code "14") (name "Net-(D7-K)") (class "Default")
      (node (ref "C20") (pin "2") (pinfunction "2_2") (pintype "passive"))
      (node (ref "D7") (pin "1") (pinfunction "K_1") (pintype "bidirectional"))
      (node (ref "IC3") (pin "6") (pinfunction "SW_6") (pintype "bidirectional"))
      (node (ref "L2") (pin "2") (pinfunction "2_2") (pintype "bidirectional"))
    )
    (net (code "15") (name "Net-(D8-K)") (class "Default")
      (node (ref "D8") (pin "1") (pinfunction "K_1") (pintype "bidirectional"))
      (node (ref "D9") (pin "2") (pinfunction "A_2") (pintype "bidirectional"))
    )
    (net (code "16") (name "Net-(D9-K)") (class "Default")
      (node (ref "C32") (pin "2") (pinfunction "2_2") (pintype "passive"))
      (node (ref "D9") (pin "1") (pinfunction "K_1") (pintype "bidirectional"))
      (node (ref "PS1") (pin "3") (pinfunction "_+VIN_3") (pintype "bidirectional"))
    )
    (net (code "17") (name "Net-(D10-C)") (class "Default")
      (node (ref "C3") (pin "1") (pinfunction "1_1") (pintype "passive"))
      (node (ref "D10") (pin "1") (pinfunction "C_1") (pintype "passive"))
      (node (ref "R37") (pin "1") (pinfunction "1_1") (pintype "passive"))
    )
    (net (code "18") (name "Net-(D11-C)") (class "Default")
      (node (ref "C36") (pin "1") (pinfunction "1_1") (pintype "passive"))
      (node (ref "D11") (pin "1") (pinfunction "C_1") (pintype "passive"))
      (node (ref "R38") (pin "1") (pinfunction "1_1") (pintype "passive"))
    )
    (net (code "19") (name "Net-(HVLED-PadA)") (class "Default")
      (node (ref "HVLED") (pin "A") (pinfunction "A_A") (pintype "passive"))
      (node (ref "R30") (pin "1") (pinfunction "1_1") (pintype "passive"))
    )
    (net (code "20") (name "Net-(IC1-ENA)") (class "Default")
      (node (ref "IC1") (pin "1") (pinfunction "ENA_1") (pintype "bidirectional"))
      (node (ref "IC1") (pin "8") (pinfunction "ENB_8") (pintype "bidirectional"))
      (node (ref "R4") (pin "1") (pinfunction "1_1") (pintype "passive"))
    )
    (net (code "21") (name "Net-(IC1-INA)") (class "Default")
      (node (ref "IC1") (pin "2") (pinfunction "INA_2") (pintype "bidirectional"))
      (node (ref "IC2") (pin "7") (pinfunction "OUTA_7") (pintype "bidirectional"))
    )
    (net (code "22") (name "Net-(IC1-INB)") (class "Default")
      (node (ref "IC1") (pin "4") (pinfunction "INB_4") (pintype "bidirectional"))
      (node (ref "IC2") (pin "6") (pinfunction "OUTB_6") (pintype "bidirectional"))
    )
    (net (code "23") (name "Net-(IC1-OUT1)") (class "Default")
      (node (ref "IC1") (pin "7") (pinfunction "OUT1_7") (pintype "bidirectional"))
      (node (ref "R2") (pin "1") (pinfunction "1_1") (pintype "passive"))
      (node (ref "R3") (pin "1") (pinfunction "1_1") (pintype "passive"))
    )
    (net (code "24") (name "Net-(IC1-OUT2)") (class "Default")
      (node (ref "IC1") (pin "5") (pinfunction "OUT2_5") (pintype "bidirectional"))
      (node (ref "R7") (pin "1") (pinfunction "1_1") (pintype "passive"))
      (node (ref "R8") (pin "1") (pinfunction "1_1") (pintype "passive"))
    )
    (net (code "25") (name "Net-(IC2-CS)") (class "Default")
      (node (ref "C16") (pin "1") (pinfunction "1_1") (pintype "passive"))
      (node (ref "IC2") (pin "3") (pinfunction "CS_3") (pintype "bidirectional"))
      (node (ref "R11") (pin "1") (pinfunction "1_1") (pintype "passive"))
    )
    (net (code "26") (name "Net-(IC2-ISET)") (class "Default")
      (node (ref "IC2") (pin "2") (pinfunction "ISET_2") (pintype "bidirectional"))
      (node (ref "R13") (pin "1") (pinfunction "1_1") (pintype "passive"))
    )
    (net (code "27") (name "Net-(IC2-RT)") (class "Default")
      (node (ref "IC2") (pin "4") (pinfunction "RT_4") (pintype "bidirectional"))
      (node (ref "R14") (pin "1") (pinfunction "1_1") (pintype "passive"))
    )
    (net (code "28") (name "Net-(IC3-BS)") (class "Default")
      (node (ref "C20") (pin "1") (pinfunction "1_1") (pintype "passive"))
      (node (ref "IC3") (pin "1") (pinfunction "BS_1") (pintype "bidirectional"))
    )
    (net (code "29") (name "Net-(IC3-EN)") (class "Default")
      (node (ref "IC3") (pin "4") (pinfunction "EN_4") (pintype "bidirectional"))
      (node (ref "R20") (pin "2") (pinfunction "2_2") (pintype "passive"))
    )
    (net (code "30") (name "Net-(IC3-FB)") (class "Default")
      (node (ref "C19") (pin "2") (pinfunction "2_2") (pintype "passive"))
      (node (ref "IC3") (pin "3") (pinfunction "FB_3") (pintype "bidirectional"))
      (node (ref "R18") (pin "2") (pinfunction "2_2") (pintype "passive"))
      (node (ref "R19") (pin "1") (pinfunction "1_1") (pintype "passive"))
    )
    (net (code "31") (name "Net-(IC4-BS)") (class "Default")
      (node (ref "C27") (pin "2") (pinfunction "2_2") (pintype "passive"))
      (node (ref "IC4") (pin "1") (pinfunction "BS_1") (pintype "bidirectional"))
    )
    (net (code "32") (name "Net-(IC4-EN)") (class "Default")
      (node (ref "IC4") (pin "4") (pinfunction "EN_4") (pintype "bidirectional"))
      (node (ref "R33") (pin "2") (pinfunction "2_2") (pintype "passive"))
    )
    (net (code "33") (name "Net-(IC4-FB)") (class "Default")
      (node (ref "C25") (pin "2") (pinfunction "2_2") (pintype "passive"))
      (node (ref "IC4") (pin "3") (pinfunction "FB_3") (pintype "bidirectional"))
      (node (ref "R31") (pin "1") (pinfunction "1_1") (pintype "passive"))
      (node (ref "R32") (pin "1") (pinfunction "1_1") (pintype "passive"))
    )
    (net (code "34") (name "Net-(IC5-CATHODE)") (class "Default")
      (node (ref "C18") (pin "2") (pinfunction "2_2") (pintype "passive"))
      (node (ref "IC5") (pin "1") (pinfunction "CATHODE_1") (pintype "bidirectional"))
      (node (ref "OPT1") (pin "2") (pinfunction "K_2") (pintype "bidirectional"))
      (node (ref "R15") (pin "1") (pinfunction "1_1") (pintype "passive"))
    )
    (net (code "35") (name "Net-(IC5-REF)") (class "Default")
      (node (ref "C17") (pin "1") (pinfunction "1_1") (pintype "passive"))
      (node (ref "C18") (pin "1") (pinfunction "1_1") (pintype "passive"))
      (node (ref "IC5") (pin "2") (pinfunction "REF_2") (pintype "bidirectional"))
      (node (ref "J2") (pin "1") (pinfunction "1_1") (pintype "passive"))
      (node (ref "R22") (pin "2") (pinfunction "2_2") (pintype "passive"))
      (node (ref "R23") (pin "2") (pinfunction "2_2") (pintype "passive"))
    )
    (net (code "36") (name "Net-(OPT1-A)") (class "Default")
      (node (ref "OPT1") (pin "1") (pinfunction "A_1") (pintype "bidirectional"))
      (node (ref "R35") (pin "2") (pinfunction "2_2") (pintype "passive"))
    )
    (net (code "37") (name "Net-(Q1-G)") (class "Default")
      (node (ref "GATE1_TP") (pin "TP") (pinfunction "TP_TP") (pintype "input"))
      (node (ref "Q1") (pin "1") (pinfunction "G_1") (pintype "bidirectional"))
      (node (ref "R2") (pin "2") (pinfunction "2_2") (pintype "passive"))
      (node (ref "R3") (pin "2") (pinfunction "2_2") (pintype "passive"))
    )
    (net (code "38") (name "Net-(Q2-G)") (class "Default")
      (node (ref "GATE2_TP") (pin "TP") (pinfunction "TP_TP") (pintype "input"))
      (node (ref "Q2") (pin "1") (pinfunction "G_1") (pintype "bidirectional"))
      (node (ref "R7") (pin "2") (pinfunction "2_2") (pintype "passive"))
      (node (ref "R8") (pin "2") (pinfunction "2_2") (pintype "passive"))
    )
    (net (code "39") (name "Net-(R21-Pad2)") (class "Default")
      (node (ref "R21") (pin "2") (pinfunction "2_2") (pintype "passive"))
      (node (ref "R22") (pin "1") (pinfunction "1_1") (pintype "passive"))
    )
    (net (code "40") (name "Net-(R23-Pad1)") (class "Default")
      (node (ref "R23") (pin "1") (pinfunction "1_1") (pintype "passive"))
      (node (ref "R24") (pin "2") (pinfunction "2_2") (pintype "passive"))
    )
    (net (code "41") (name "Net-(R24-Pad1)") (class "Default")
      (node (ref "R24") (pin "1") (pinfunction "1_1") (pintype "passive"))
      (node (ref "R25") (pin "2") (pinfunction "2_2") (pintype "passive"))
    )
    (net (code "42") (name "Net-(R26-Pad1)") (class "Default")
      (node (ref "R26") (pin "1") (pinfunction "1_1") (pintype "passive"))
      (node (ref "R27") (pin "2") (pinfunction "2_2") (pintype "passive"))
    )
    (net (code "43") (name "Net-(R27-Pad1)") (class "Default")
      (node (ref "R27") (pin "1") (pinfunction "1_1") (pintype "passive"))
      (node (ref "R28") (pin "2") (pinfunction "2_2") (pintype "passive"))
    )
    (net (code "44") (name "Net-(R28-Pad1)") (class "Default")
      (node (ref "R28") (pin "1") (pinfunction "1_1") (pintype "passive"))
      (node (ref "R29") (pin "2") (pinfunction "2_2") (pintype "passive"))
    )
    (net (code "45") (name "Net-(R29-Pad1)") (class "Default")
      (node (ref "R29") (pin "1") (pinfunction "1_1") (pintype "passive"))
      (node (ref "R30") (pin "2") (pinfunction "2_2") (pintype "passive"))
    )
    (net (code "46") (name "Net-(SJ100-Pad1)") (class "Default")
      (node (ref "SJ100") (pin "1") (pinfunction "1_1") (pintype "passive"))
      (node (ref "T1") (pin "11") (pinfunction "11_11") (pintype "bidirectional"))
    )
    (net (code "47") (name "Net-(SJ100-Pad3)") (class "Default")
      (node (ref "SJ100") (pin "3") (pinfunction "3_3") (pintype "passive"))
      (node (ref "T1") (pin "13") (pinfunction "13_13") (pintype "bidirectional"))
    )
    (net (code "48") (name "Net-(VR1-ADJ)") (class "Default")
      (node (ref "R10") (pin "1") (pinfunction "1_1") (pintype "passive"))
      (node (ref "R9") (pin "2") (pinfunction "2_2") (pintype "passive"))
      (node (ref "VR1") (pin "1") (pinfunction "ADJ_1") (pintype "input"))
    )
    (net (code "49") (name "OPTO-EMITT") (class "Default")
      (node (ref "IC2") (pin "1") (pinfunction "CTRL_1") (pintype "bidirectional"))
      (node (ref "OPT1") (pin "4") (pinfunction "C_4") (pintype "bidirectional"))
      (node (ref "R12") (pin "2") (pinfunction "2_2") (pintype "passive"))
    )
    (net (code "50") (name "PRE") (class "Default")
      (node (ref "C25") (pin "1") (pinfunction "1_1") (pintype "passive"))
      (node (ref "C28") (pin "2") (pinfunction "2_2") (pintype "passive"))
      (node (ref "C29") (pin "2") (pinfunction "2_2") (pintype "passive"))
      (node (ref "C30") (pin "2") (pinfunction "2_2") (pintype "passive"))
      (node (ref "L3") (pin "2") (pinfunction "2_2") (pintype "bidirectional"))
      (node (ref "MAINBUCK_TP") (pin "TP") (pinfunction "TP_TP") (pintype "input"))
      (node (ref "R32") (pin "2") (pinfunction "2_2") (pintype "passive"))
      (node (ref "VR1") (pin "3") (pinfunction "IN_3") (pintype "input"))
    )
    (net (code "51") (name "PWRGND") (class "Default")
      (node (ref "C21") (pin "2") (pinfunction "2_2") (pintype "passive"))
      (node (ref "C22") (pin "1") (pinfunction "1_1") (pintype "passive"))
      (node (ref "C23") (pin "1") (pinfunction "1_1") (pintype "passive"))
      (node (ref "C24") (pin "1") (pinfunction "1_1") (pintype "passive"))
      (node (ref "C33") (pin "1") (pinfunction "1_1") (pintype "passive"))
      (node (ref "C34") (pin "2") (pinfunction "2_2") (pintype "passive"))
      (node (ref "C35") (pin "1") (pinfunction "1_1") (pintype "passive"))
      (node (ref "C4") (pin "2") (pinfunction "2_2") (pintype "bidirectional"))
      (node (ref "C5") (pin "2") (pinfunction "2_2") (pintype "bidirectional"))
      (node (ref "C6") (pin "2") (pinfunction "-_2") (pintype "bidirectional"))
      (node (ref "C7") (pin "2") (pinfunction "-_2") (pintype "bidirectional"))
      (node (ref "D1") (pin "1") (pinfunction "A1_1") (pintype "bidirectional"))
      (node (ref "D1") (pin "3") (pinfunction "A2_3") (pintype "bidirectional"))
      (node (ref "D3") (pin "1") (pinfunction "A1_1") (pintype "bidirectional"))
      (node (ref "D3") (pin "3") (pinfunction "A2_3") (pintype "bidirectional"))
      (node (ref "D7") (pin "2") (pinfunction "A_2") (pintype "bidirectional"))
      (node (ref "HVLED") (pin "C") (pinfunction "C_C") (pintype "passive"))
      (node (ref "IC3") (pin "2") (pinfunction "GND_2") (pintype "bidirectional"))
      (node (ref "IC5") (pin "3") (pinfunction "ANODE_3") (pintype "bidirectional"))
      (node (ref "J1") (pin "1") (pinfunction "1_1") (pintype "bidirectional"))
      (node (ref "J2") (pin "2") (pinfunction "2_2") (pintype "passive"))
      (node (ref "PS1") (pin "7") (pinfunction "-VOUT_7") (pintype "bidirectional"))
      (node (ref "PWRGND_TP") (pin "TP") (pinfunction "TP_TP") (pintype "input"))
      (node (ref "R19") (pin "2") (pinfunction "2_2") (pintype "passive"))
      (node (ref "R21") (pin "1") (pinfunction "1_1") (pintype "passive"))
      (node (ref "R36") (pin "1") (pinfunction "1_1") (pintype "passive"))
      (node (ref "T1") (pin "15") (pinfunction "15_15") (pintype "bidirectional"))
      (node (ref "T1.1") (pin "4") (pinfunction "4_4") (pintype "bidirectional"))
      (node (ref "VR2") (pin "1") (pinfunction "GND_1") (pintype "bidirectional"))
      (node (ref "Z3") (pin "2") (pinfunction "A_2") (pintype "bidirectional"))
    )
    (net (code "52") (name "RECT") (class "Default")
      (node (ref "D2") (pin "2") (pinfunction "K_2") (pintype "bidirectional"))
      (node (ref "D4") (pin "2") (pinfunction "K_2") (pintype "bidirectional"))
      (node (ref "L1") (pin "1") (pinfunction "1_1") (pintype "bidirectional"))
    )
    (net (code "53") (name "REG") (class "Default")
      (node (ref "13.75V") (pin "A") (pinfunction "A_A") (pintype "passive"))
      (node (ref "13.75V_TP") (pin "TP") (pinfunction "TP_TP") (pintype "input"))
      (node (ref "C10") (pin "1") (pinfunction "1_1") (pintype "passive"))
      (node (ref "C14") (pin "1") (pinfunction "1_1") (pintype "passive"))
      (node (ref "C15") (pin "1") (pinfunction "1_1") (pintype "passive"))
      (node (ref "C31") (pin "2") (pinfunction "2_2") (pintype "passive"))
      (node (ref "C9") (pin "1") (pinfunction "1_1") (pintype "passive"))
      (node (ref "D8") (pin "2") (pinfunction "A_2") (pintype "bidirectional"))
      (node (ref "IC1") (pin "6") (pinfunction "VDD_6") (pintype "bidirectional"))
      (node (ref "IC2") (pin "8") (pinfunction "VDD_8") (pintype "bidirectional"))
      (node (ref "R10") (pin "2") (pinfunction "2_2") (pintype "passive"))
      (node (ref "R12") (pin "1") (pinfunction "1_1") (pintype "passive"))
      (node (ref "R4") (pin "2") (pinfunction "2_2") (pintype "passive"))
      (node (ref "VR1") (pin "4") (pinfunction "OUT_4") (pintype "passive"))
    )
    (net (code "54") (name "REG5V") (class "Default")
      (node (ref "5VLED") (pin "A") (pinfunction "A_A") (pintype "passive"))
      (node (ref "AUX5V_TP") (pin "TP") (pinfunction "TP_TP") (pintype "input"))
      (node (ref "C33") (pin "2") (pinfunction "2_2") (pintype "passive"))
      (node (ref "C35") (pin "2") (pinfunction "2_2") (pintype "passive"))
      (node (ref "PS1") (pin "8") (pinfunction "+VOUT_8") (pintype "bidirectional"))
      (node (ref "R35") (pin "1") (pinfunction "1_1") (pintype "passive"))
      (node (ref "VR2") (pin "2") (pinfunction "VOUT_2") (pintype "bidirectional"))
    )
    (net (code "55") (name "TRANS1") (class "Default")
      (node (ref "D1") (pin "2") (pinfunction "K_2") (pintype "bidirectional"))
      (node (ref "D2") (pin "1") (pinfunction "A1_1") (pintype "bidirectional"))
      (node (ref "D2") (pin "3") (pinfunction "A2_3") (pintype "bidirectional"))
      (node (ref "SJ100") (pin "2") (pinfunction "2_2") (pintype "passive"))
      (node (ref "T1.1") (pin "8") (pinfunction "8_8") (pintype "bidirectional"))
    )
    (net (code "56") (name "TRANS2") (class "Default")
      (node (ref "D3") (pin "2") (pinfunction "K_2") (pintype "bidirectional"))
      (node (ref "D4") (pin "1") (pinfunction "A1_1") (pintype "bidirectional"))
      (node (ref "D4") (pin "3") (pinfunction "A2_3") (pintype "bidirectional"))
      (node (ref "T1") (pin "9") (pinfunction "9_9") (pintype "bidirectional"))
      (node (ref "T1.1") (pin "14") (pinfunction "14_14") (pintype "bidirectional"))
    )
    (net (code "57") (name "VCC28V") (class "Default")
      (node (ref "C1") (pin "1") (pinfunction "+_1") (pintype "bidirectional"))
      (node (ref "C11") (pin "2") (pinfunction "2_2") (pintype "passive"))
      (node (ref "C12") (pin "1") (pinfunction "+_1") (pintype "bidirectional"))
      (node (ref "C13") (pin "1") (pinfunction "+_1") (pintype "bidirectional"))
      (node (ref "C2") (pin "1") (pinfunction "+_1") (pintype "bidirectional"))
      (node (ref "C26") (pin "1") (pinfunction "1_1") (pintype "passive"))
      (node (ref "C3") (pin "2") (pinfunction "2_2") (pintype "passive"))
      (node (ref "C36") (pin "2") (pinfunction "2_2") (pintype "passive"))
      (node (ref "C8") (pin "1") (pinfunction "1_1") (pintype "passive"))
      (node (ref "IC4") (pin "5") (pinfunction "IN_5") (pintype "bidirectional"))
      (node (ref "INPUT") (pin "1") (pinfunction "1_1") (pintype "bidirectional"))
      (node (ref "R33") (pin "1") (pinfunction "1_1") (pintype "passive"))
      (node (ref "R37") (pin "2") (pinfunction "2_2") (pintype "passive"))
      (node (ref "R38") (pin "2") (pinfunction "2_2") (pintype "passive"))
      (node (ref "T1") (pin "4") (pinfunction "4_4") (pintype "bidirectional"))
      (node (ref "T1") (pin "5") (pinfunction "5_5") (pintype "bidirectional"))
      (node (ref "T1.1") (pin "7") (pinfunction "7_7") (pintype "bidirectional"))
    )
    (net (code "58") (name "unconnected-(PS1-NA-Pad14)") (class "Default")
      (node (ref "PS1") (pin "14") (pinfunction "NA_14") (pintype "bidirectional"))
    )
    (net (code "59") (name "unconnected-(T1-Pad10)") (class "Default")
      (node (ref "T1") (pin "10") (pinfunction "10_10") (pintype "bidirectional"))
    )
    (net (code "60") (name "unconnected-(T1-Pad12)") (class "Default")
      (node (ref "T1") (pin "12") (pinfunction "12_12") (pintype "bidirectional"))
    )
    (net (code "61") (name "unconnected-(T1-Pad14)") (class "Default")
      (node (ref "T1") (pin "14") (pinfunction "14_14") (pintype "bidirectional"))
    )
    (net (code "62") (name "unconnected-(T1.1-Pad6)") (class "Default")
      (node (ref "T1.1") (pin "6") (pinfunction "6_6") (pintype "bidirectional"))
    )
    (net (code "63") (name "unconnected-(T1.1-Pad10)") (class "Default")
      (node (ref "T1.1") (pin "10") (pinfunction "10_10") (pintype "bidirectional"))
    )
    (net (code "64") (name "unconnected-(T1.1-Pad12)") (class "Default")
      (node (ref "T1.1") (pin "12") (pinfunction "12_12") (pintype "bidirectional"))
    )
  )
)
